# sb2.net
KiCad netlist of a schematic drawn in EAGLE
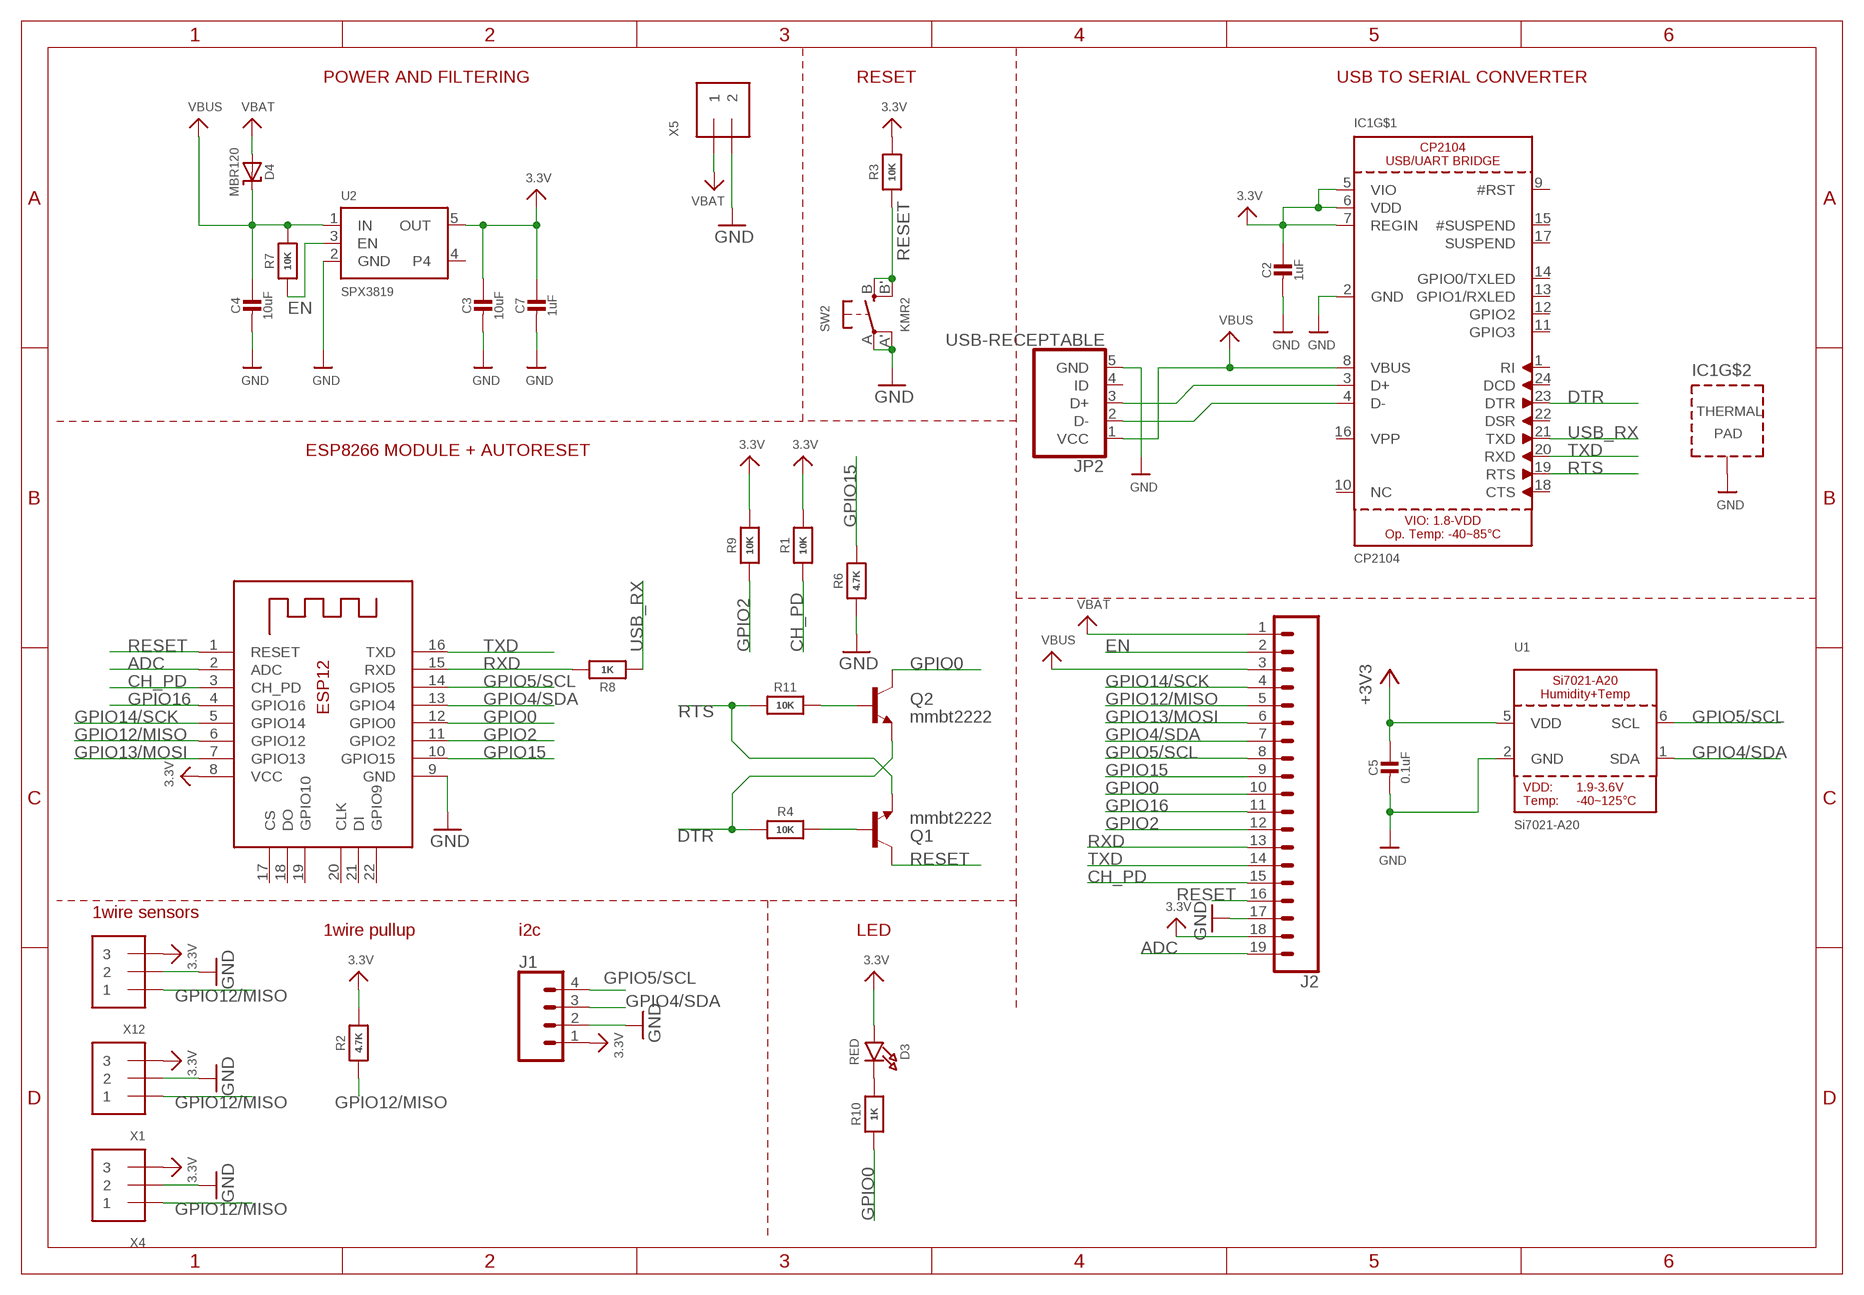
[diagram p0: schematic, sheet 1]

(export (version "E")
  (design (tool "Eeschema 10.0.6"))
  (components
    (comp (ref "C2")
      (value "1uF")
      (footprint "eagle-import:0603-NO")
      (libsource (lib "eagle-import") (part "CAP_CERAMIC0603_NO"))
    )
    (comp (ref "C3")
      (value "10uF")
      (footprint "eagle-import:0603-NO")
      (libsource (lib "eagle-import") (part "CAP_CERAMIC0603_NO"))
    )
    (comp (ref "C4")
      (value "10uF")
      (footprint "eagle-import:0603-NO")
      (libsource (lib "eagle-import") (part "CAP_CERAMIC0603_NO"))
    )
    (comp (ref "C5")
      (value "0.1uF")
      (footprint "eagle-import:0603-NO")
      (libsource (lib "eagle-import") (part "CAP_CERAMIC0603_NO"))
    )
    (comp (ref "C7")
      (value "1uF")
      (footprint "eagle-import:0603-NO")
      (libsource (lib "eagle-import") (part "CAP_CERAMIC0603_NO"))
    )
    (comp (ref "D3")
      (value "RED")
      (footprint "eagle-import:CHIPLED_0805_NOOUTLINE")
      (libsource (lib "eagle-import") (part "LED0805_NOOUTLINE"))
    )
    (comp (ref "D4")
      (value "MBR120")
      (footprint "eagle-import:SOD-123")
      (libsource (lib "eagle-import") (part "DIODE-SCHOTTKYSOD-123"))
    )
    (comp (ref "IC1")
      (value "CP2104")
      (footprint "eagle-import:QFN24_4MM_SMSC")
      (libsource (lib "eagle-import") (part "CP2104"))
    )
    (comp (ref "J1")
      (value "CONN_04SCREW")
      (footprint "eagle-import:SCREWTERMINAL-3.5MM-4")
      (libsource (lib "eagle-import") (part "CONN_04SCREW"))
    )
    (comp (ref "J2")
      (value "CONN_19")
      (footprint "eagle-import:1X19")
      (libsource (lib "eagle-import") (part "CONN_19"))
    )
    (comp (ref "JP2")
      (value "USB-RECEPTABLE")
      (footprint "eagle-import:FCI-10103594-0001LF")
      (libsource (lib "eagle-import") (part "USB-RECEPTABLE"))
    )
    (comp (ref "Q1")
      (value "mmbt2222")
      (footprint "eagle-import:SOT23-3")
      (libsource (lib "eagle-import") (part "TRANSISTOR_NPNSOT23-3"))
    )
    (comp (ref "Q2")
      (value "mmbt2222")
      (footprint "eagle-import:SOT23-3")
      (libsource (lib "eagle-import") (part "TRANSISTOR_NPNSOT23-3"))
    )
    (comp (ref "R1")
      (value "10K")
      (footprint "eagle-import:0603-NO")
      (libsource (lib "eagle-import") (part "RESISTOR_0603_NOOUT"))
    )
    (comp (ref "R2")
      (value "4.7K")
      (footprint "eagle-import:0603-NO")
      (libsource (lib "eagle-import") (part "RESISTOR_0603_NOOUT"))
    )
    (comp (ref "R3")
      (value "10K")
      (footprint "eagle-import:0603-NO")
      (libsource (lib "eagle-import") (part "RESISTOR_0603_NOOUT"))
    )
    (comp (ref "R4")
      (value "10K")
      (footprint "eagle-import:0603-NO")
      (libsource (lib "eagle-import") (part "RESISTOR_0603_NOOUT"))
    )
    (comp (ref "R6")
      (value "4.7K")
      (footprint "eagle-import:0603-NO")
      (libsource (lib "eagle-import") (part "RESISTOR_0603_NOOUT"))
    )
    (comp (ref "R7")
      (value "10K")
      (footprint "eagle-import:0603-NO")
      (libsource (lib "eagle-import") (part "RESISTOR_0603_NOOUT"))
    )
    (comp (ref "R8")
      (value "1K")
      (footprint "eagle-import:0603-NO")
      (libsource (lib "eagle-import") (part "RESISTOR_0603_NOOUT"))
    )
    (comp (ref "R9")
      (value "10K")
      (footprint "eagle-import:0603-NO")
      (libsource (lib "eagle-import") (part "RESISTOR_0603_NOOUT"))
    )
    (comp (ref "R10")
      (value "1K")
      (footprint "eagle-import:0603-NO")
      (libsource (lib "eagle-import") (part "RESISTOR_0603_NOOUT"))
    )
    (comp (ref "R11")
      (value "10K")
      (footprint "eagle-import:0603-NO")
      (libsource (lib "eagle-import") (part "RESISTOR_0603_NOOUT"))
    )
    (comp (ref "SW2")
      (value "KMR2")
      (footprint "eagle-import:BTN_KMR2_4.6X2.8")
      (libsource (lib "eagle-import") (part "SWITCH_TACT_SMT4.6X2.8"))
    )
    (comp (ref "U1")
      (value "Si7021-A20")
      (footprint "eagle-import:DFN6_3X3_SI")
      (libsource (lib "eagle-import") (part "SI7021-A20"))
    )
    (comp (ref "U2")
      (value "SPX3819")
      (footprint "eagle-import:SOT23-5")
      (libsource (lib "eagle-import") (part "VREG_SOT23-5"))
    )
    (comp (ref "X1")
      (value "TERMBLOCK_1X3")
      (footprint "eagle-import:TERMBLOCK_1X3-3.5MM")
      (libsource (lib "eagle-import") (part "TERMBLOCK_1X3"))
    )
    (comp (ref "X2")
      (value "ESP-12")
      (footprint "eagle-import:ESP-12E")
      (libsource (lib "eagle-import") (part "ESP-12E"))
    )
    (comp (ref "X4")
      (value "TERMBLOCK_1X3")
      (footprint "eagle-import:TERMBLOCK_1X3-3.5MM")
      (libsource (lib "eagle-import") (part "TERMBLOCK_1X3"))
    )
    (comp (ref "X5")
      (value "TERMBLOCK_1X2")
      (footprint "eagle-import:TERMBLOCK_1X2-3.5MM")
      (libsource (lib "eagle-import") (part "TERMBLOCK_1X2"))
    )
    (comp (ref "X12")
      (value "TERMBLOCK_1X3")
      (footprint "eagle-import:TERMBLOCK_1X3-3.5MM")
      (libsource (lib "eagle-import") (part "TERMBLOCK_1X3"))
    )
  )
  (nets
    (net (code "1") (name "+3V3") (class "Default")
      (node (ref "C5") (pin "1") (pinfunction "1_1") (pintype "passive"))
      (node (ref "U1") (pin "5") (pinfunction "VDD_5") (pintype "power_in"))
    )
    (net (code "2") (name "/ADC") (class "Default")
      (node (ref "J2") (pin "19") (pinfunction "19_19") (pintype "passive"))
      (node (ref "X2") (pin "2") (pinfunction "ADC_2") (pintype "passive"))
    )
    (net (code "3") (name "/CH_PD") (class "Default")
      (node (ref "J2") (pin "15") (pinfunction "15_15") (pintype "passive"))
      (node (ref "R1") (pin "1") (pinfunction "1_1") (pintype "passive"))
      (node (ref "X2") (pin "3") (pinfunction "CH_PD_3") (pintype "input"))
    )
    (net (code "4") (name "/DTR") (class "Default")
      (node (ref "IC1") (pin "23") (pinfunction "DTR_23") (pintype "output"))
      (node (ref "Q2") (pin "2") (pinfunction "E_2") (pintype "passive"))
      (node (ref "R4") (pin "1") (pinfunction "1_1") (pintype "passive"))
    )
    (net (code "5") (name "/EN") (class "Default")
      (node (ref "J2") (pin "2") (pinfunction "2_2") (pintype "passive"))
      (node (ref "R7") (pin "1") (pinfunction "1_1") (pintype "passive"))
      (node (ref "U2") (pin "3") (pinfunction "EN_3") (pintype "input"))
    )
    (net (code "6") (name "/GPIO0") (class "Default")
      (node (ref "J2") (pin "10") (pinfunction "10_10") (pintype "passive"))
      (node (ref "Q2") (pin "3") (pinfunction "C_3") (pintype "passive"))
      (node (ref "R10") (pin "1") (pinfunction "1_1") (pintype "passive"))
      (node (ref "X2") (pin "12") (pinfunction "GPIO0_12") (pintype "bidirectional"))
    )
    (net (code "7") (name "/GPIO2") (class "Default")
      (node (ref "J2") (pin "12") (pinfunction "12_12") (pintype "passive"))
      (node (ref "R9") (pin "1") (pinfunction "1_1") (pintype "passive"))
      (node (ref "X2") (pin "11") (pinfunction "GPIO2_11") (pintype "bidirectional"))
    )
    (net (code "8") (name "/GPIO4{slash}SDA") (class "Default")
      (node (ref "J1") (pin "3") (pinfunction "3_3") (pintype "passive"))
      (node (ref "J2") (pin "7") (pinfunction "7_7") (pintype "passive"))
      (node (ref "U1") (pin "1") (pinfunction "SDA_1") (pintype "open_collector"))
      (node (ref "X2") (pin "13") (pinfunction "GPIO4_13") (pintype "bidirectional"))
    )
    (net (code "9") (name "/GPIO5{slash}SCL") (class "Default")
      (node (ref "J1") (pin "4") (pinfunction "4_4") (pintype "passive"))
      (node (ref "J2") (pin "8") (pinfunction "8_8") (pintype "passive"))
      (node (ref "U1") (pin "6") (pinfunction "SCL_6") (pintype "open_collector"))
      (node (ref "X2") (pin "14") (pinfunction "GPIO5_14") (pintype "bidirectional"))
    )
    (net (code "10") (name "/GPIO12{slash}MISO") (class "Default")
      (node (ref "J2") (pin "5") (pinfunction "5_5") (pintype "passive"))
      (node (ref "R2") (pin "1") (pinfunction "1_1") (pintype "passive"))
      (node (ref "X1") (pin "1") (pinfunction "1_1") (pintype "passive"))
      (node (ref "X12") (pin "1") (pinfunction "1_1") (pintype "passive"))
      (node (ref "X2") (pin "6") (pinfunction "GPIO12_6") (pintype "bidirectional"))
      (node (ref "X4") (pin "1") (pinfunction "1_1") (pintype "passive"))
    )
    (net (code "11") (name "/GPIO13{slash}MOSI") (class "Default")
      (node (ref "J2") (pin "6") (pinfunction "6_6") (pintype "passive"))
      (node (ref "X2") (pin "7") (pinfunction "GPIO13_7") (pintype "bidirectional"))
    )
    (net (code "12") (name "/GPIO14{slash}SCK") (class "Default")
      (node (ref "J2") (pin "4") (pinfunction "4_4") (pintype "passive"))
      (node (ref "X2") (pin "5") (pinfunction "GPIO14_5") (pintype "bidirectional"))
    )
    (net (code "13") (name "/GPIO15") (class "Default")
      (node (ref "J2") (pin "9") (pinfunction "9_9") (pintype "passive"))
      (node (ref "R6") (pin "2") (pinfunction "2_2") (pintype "passive"))
      (node (ref "X2") (pin "10") (pinfunction "GPIO15_10") (pintype "bidirectional"))
    )
    (net (code "14") (name "/GPIO16") (class "Default")
      (node (ref "J2") (pin "11") (pinfunction "11_11") (pintype "passive"))
      (node (ref "X2") (pin "4") (pinfunction "GPIO16_4") (pintype "bidirectional"))
    )
    (net (code "15") (name "/RESET") (class "Default")
      (node (ref "J2") (pin "16") (pinfunction "16_16") (pintype "passive"))
      (node (ref "Q1") (pin "3") (pinfunction "C_3") (pintype "passive"))
      (node (ref "R3") (pin "1") (pinfunction "1_1") (pintype "passive"))
      (node (ref "SW2") (pin "B") (pinfunction "S_B") (pintype "passive"))
      (node (ref "SW2") (pin "B'") (pinfunction "S1_B'") (pintype "passive"))
      (node (ref "X2") (pin "1") (pinfunction "RESET_1") (pintype "input"))
    )
    (net (code "16") (name "/RTS") (class "Default")
      (node (ref "IC1") (pin "19") (pinfunction "RTS_19") (pintype "output"))
      (node (ref "Q1") (pin "2") (pinfunction "E_2") (pintype "passive"))
      (node (ref "R11") (pin "1") (pinfunction "1_1") (pintype "passive"))
    )
    (net (code "17") (name "/RXD") (class "Default")
      (node (ref "J2") (pin "13") (pinfunction "13_13") (pintype "passive"))
      (node (ref "R8") (pin "2") (pinfunction "2_2") (pintype "passive"))
      (node (ref "X2") (pin "15") (pinfunction "RXD_15") (pintype "input"))
    )
    (net (code "18") (name "/TXD") (class "Default")
      (node (ref "IC1") (pin "20") (pinfunction "RXD_20") (pintype "input"))
      (node (ref "J2") (pin "14") (pinfunction "14_14") (pintype "passive"))
      (node (ref "X2") (pin "16") (pinfunction "TXD_16") (pintype "output"))
    )
    (net (code "19") (name "/USB_RX") (class "Default")
      (node (ref "IC1") (pin "21") (pinfunction "TXD_21") (pintype "output"))
      (node (ref "R8") (pin "1") (pinfunction "1_1") (pintype "passive"))
    )
    (net (code "20") (name "3.3V") (class "Default")
      (node (ref "C2") (pin "1") (pinfunction "1_1") (pintype "passive"))
      (node (ref "C3") (pin "1") (pinfunction "1_1") (pintype "passive"))
      (node (ref "C7") (pin "1") (pinfunction "1_1") (pintype "passive"))
      (node (ref "D3") (pin "A") (pinfunction "A_A") (pintype "passive"))
      (node (ref "IC1") (pin "5") (pinfunction "VIO_5") (pintype "power_in"))
      (node (ref "IC1") (pin "6") (pinfunction "VDD_6") (pintype "power_in"))
      (node (ref "IC1") (pin "7") (pinfunction "REGIN_7") (pintype "power_in"))
      (node (ref "J1") (pin "1") (pinfunction "1_1") (pintype "passive"))
      (node (ref "J2") (pin "18") (pinfunction "18_18") (pintype "passive"))
      (node (ref "R1") (pin "2") (pinfunction "2_2") (pintype "passive"))
      (node (ref "R2") (pin "2") (pinfunction "2_2") (pintype "passive"))
      (node (ref "R3") (pin "2") (pinfunction "2_2") (pintype "passive"))
      (node (ref "R9") (pin "2") (pinfunction "2_2") (pintype "passive"))
      (node (ref "U2") (pin "5") (pinfunction "OUT_5") (pintype "power_in"))
      (node (ref "X1") (pin "3") (pinfunction "3_3") (pintype "passive"))
      (node (ref "X12") (pin "3") (pinfunction "3_3") (pintype "passive"))
      (node (ref "X2") (pin "8") (pinfunction "VCC_8") (pintype "power_in"))
      (node (ref "X4") (pin "3") (pinfunction "3_3") (pintype "passive"))
    )
    (net (code "21") (name "GND") (class "Default")
      (node (ref "C2") (pin "2") (pinfunction "2_2") (pintype "passive"))
      (node (ref "C3") (pin "2") (pinfunction "2_2") (pintype "passive"))
      (node (ref "C4") (pin "2") (pinfunction "2_2") (pintype "passive"))
      (node (ref "C5") (pin "2") (pinfunction "2_2") (pintype "passive"))
      (node (ref "C7") (pin "2") (pinfunction "2_2") (pintype "passive"))
      (node (ref "IC1") (pin "2") (pinfunction "GND_2") (pintype "power_in"))
      (node (ref "IC1") (pin "THERM") (pinfunction "TP_THERM") (pintype "power_in"))
      (node (ref "J1") (pin "2") (pinfunction "2_2") (pintype "passive"))
      (node (ref "J2") (pin "17") (pinfunction "17_17") (pintype "passive"))
      (node (ref "JP2") (pin "5") (pinfunction "GND_5") (pintype "bidirectional"))
      (node (ref "R6") (pin "1") (pinfunction "1_1") (pintype "passive"))
      (node (ref "SW2") (pin "A") (pinfunction "P_A") (pintype "passive"))
      (node (ref "SW2") (pin "A'") (pinfunction "P1_A'") (pintype "passive"))
      (node (ref "U1") (pin "2") (pinfunction "GND_2") (pintype "power_in"))
      (node (ref "U2") (pin "2") (pinfunction "GND_2") (pintype "power_in"))
      (node (ref "X1") (pin "2") (pinfunction "2_2") (pintype "passive"))
      (node (ref "X12") (pin "2") (pinfunction "2_2") (pintype "passive"))
      (node (ref "X2") (pin "9") (pinfunction "GND_9") (pintype "power_in"))
      (node (ref "X4") (pin "2") (pinfunction "2_2") (pintype "passive"))
      (node (ref "X5") (pin "2") (pinfunction "2_2") (pintype "passive"))
    )
    (net (code "22") (name "Net-(D3-PadC)") (class "Default")
      (node (ref "D3") (pin "C") (pinfunction "C_C") (pintype "passive"))
      (node (ref "R10") (pin "2") (pinfunction "2_2") (pintype "passive"))
    )
    (net (code "23") (name "Net-(IC1A-D+)") (class "Default")
      (node (ref "IC1") (pin "3") (pinfunction "D+_3") (pintype "bidirectional"))
      (node (ref "JP2") (pin "3") (pinfunction "D+_3") (pintype "bidirectional"))
    )
    (net (code "24") (name "Net-(IC1A-D-)") (class "Default")
      (node (ref "IC1") (pin "4") (pinfunction "D-_4") (pintype "bidirectional"))
      (node (ref "JP2") (pin "2") (pinfunction "D-_2") (pintype "bidirectional"))
    )
    (net (code "25") (name "Net-(Q1-B)") (class "Default")
      (node (ref "Q1") (pin "1") (pinfunction "B_1") (pintype "passive"))
      (node (ref "R4") (pin "2") (pinfunction "2_2") (pintype "passive"))
    )
    (net (code "26") (name "Net-(Q2-B)") (class "Default")
      (node (ref "Q2") (pin "1") (pinfunction "B_1") (pintype "passive"))
      (node (ref "R11") (pin "2") (pinfunction "2_2") (pintype "passive"))
    )
    (net (code "27") (name "VBAT") (class "Default")
      (node (ref "D4") (pin "A") (pinfunction "A_A") (pintype "passive"))
      (node (ref "J2") (pin "1") (pinfunction "1_1") (pintype "passive"))
      (node (ref "X5") (pin "1") (pinfunction "1_1") (pintype "passive"))
    )
    (net (code "28") (name "VBUS") (class "Default")
      (node (ref "C4") (pin "1") (pinfunction "1_1") (pintype "passive"))
      (node (ref "D4") (pin "C") (pinfunction "C_C") (pintype "passive"))
      (node (ref "IC1") (pin "8") (pinfunction "VBUS_8") (pintype "power_in"))
      (node (ref "J2") (pin "3") (pinfunction "3_3") (pintype "passive"))
      (node (ref "JP2") (pin "1") (pinfunction "VCC_1") (pintype "bidirectional"))
      (node (ref "R7") (pin "2") (pinfunction "2_2") (pintype "passive"))
      (node (ref "U2") (pin "1") (pinfunction "IN_1") (pintype "power_in"))
    )
    (net (code "29") (name "unconnected-(IC1A-#RST-Pad9)") (class "Default")
      (node (ref "IC1") (pin "9") (pinfunction "#RST_9") (pintype "bidirectional"))
    )
    (net (code "30") (name "unconnected-(IC1A-#SUSPEND-Pad15)") (class "Default")
      (node (ref "IC1") (pin "15") (pinfunction "#SUSPEND_15") (pintype "output"))
    )
    (net (code "31") (name "unconnected-(IC1A-CTS-Pad18)") (class "Default")
      (node (ref "IC1") (pin "18") (pinfunction "CTS_18") (pintype "input"))
    )
    (net (code "32") (name "unconnected-(IC1A-DCD-Pad24)") (class "Default")
      (node (ref "IC1") (pin "24") (pinfunction "DCD_24") (pintype "input"))
    )
    (net (code "33") (name "unconnected-(IC1A-DSR-Pad22)") (class "Default")
      (node (ref "IC1") (pin "22") (pinfunction "DSR_22") (pintype "input"))
    )
    (net (code "34") (name "unconnected-(IC1A-GPIO0{slash}TXLED-Pad14)") (class "Default")
      (node (ref "IC1") (pin "14") (pinfunction "GPIO0/TXLED_14") (pintype "bidirectional"))
    )
    (net (code "35") (name "unconnected-(IC1A-GPIO1{slash}RXLED-Pad13)") (class "Default")
      (node (ref "IC1") (pin "13") (pinfunction "GPIO1/RXLED_13") (pintype "bidirectional"))
    )
    (net (code "36") (name "unconnected-(IC1A-GPIO2-Pad12)") (class "Default")
      (node (ref "IC1") (pin "12") (pinfunction "GPIO2_12") (pintype "bidirectional"))
    )
    (net (code "37") (name "unconnected-(IC1A-GPIO3-Pad11)") (class "Default")
      (node (ref "IC1") (pin "11") (pinfunction "GPIO3_11") (pintype "bidirectional"))
    )
    (net (code "38") (name "unconnected-(IC1A-NC-Pad10)") (class "Default")
      (node (ref "IC1") (pin "10") (pinfunction "NC_10") (pintype "no_connect"))
    )
    (net (code "39") (name "unconnected-(IC1A-RI-Pad1)") (class "Default")
      (node (ref "IC1") (pin "1") (pinfunction "RI_1") (pintype "input"))
    )
    (net (code "40") (name "unconnected-(IC1A-SUSPEND-Pad17)") (class "Default")
      (node (ref "IC1") (pin "17") (pinfunction "SUSPEND_17") (pintype "output"))
    )
    (net (code "41") (name "unconnected-(IC1A-VPP-Pad16)") (class "Default")
      (node (ref "IC1") (pin "16") (pinfunction "VPP_16") (pintype "bidirectional"))
    )
    (net (code "42") (name "unconnected-(JP2-ID-Pad4)") (class "Default")
      (node (ref "JP2") (pin "4") (pinfunction "ID_4") (pintype "bidirectional"))
    )
    (net (code "43") (name "unconnected-(U2-P4-Pad4)") (class "Default")
      (node (ref "U2") (pin "4") (pinfunction "P4_4") (pintype "bidirectional"))
    )
    (net (code "44") (name "unconnected-(X2-CLK-Pad20)") (class "Default")
      (node (ref "X2") (pin "20") (pinfunction "CLK_20") (pintype "bidirectional"))
    )
    (net (code "45") (name "unconnected-(X2-CS-Pad17)") (class "Default")
      (node (ref "X2") (pin "17") (pinfunction "CS_17") (pintype "bidirectional"))
    )
    (net (code "46") (name "unconnected-(X2-DI-Pad21)") (class "Default")
      (node (ref "X2") (pin "21") (pinfunction "DI_21") (pintype "bidirectional"))
    )
    (net (code "47") (name "unconnected-(X2-DO-Pad18)") (class "Default")
      (node (ref "X2") (pin "18") (pinfunction "DO_18") (pintype "bidirectional"))
    )
    (net (code "48") (name "unconnected-(X2-GPIO9-Pad22)") (class "Default")
      (node (ref "X2") (pin "22") (pinfunction "GPIO9_22") (pintype "bidirectional"))
    )
    (net (code "49") (name "unconnected-(X2-GPIO10-Pad19)") (class "Default")
      (node (ref "X2") (pin "19") (pinfunction "GPIO10_19") (pintype "bidirectional"))
    )
  )
)
